# AutomatedBlindOpener.net
KiCad netlist of a schematic drawn in EAGLE
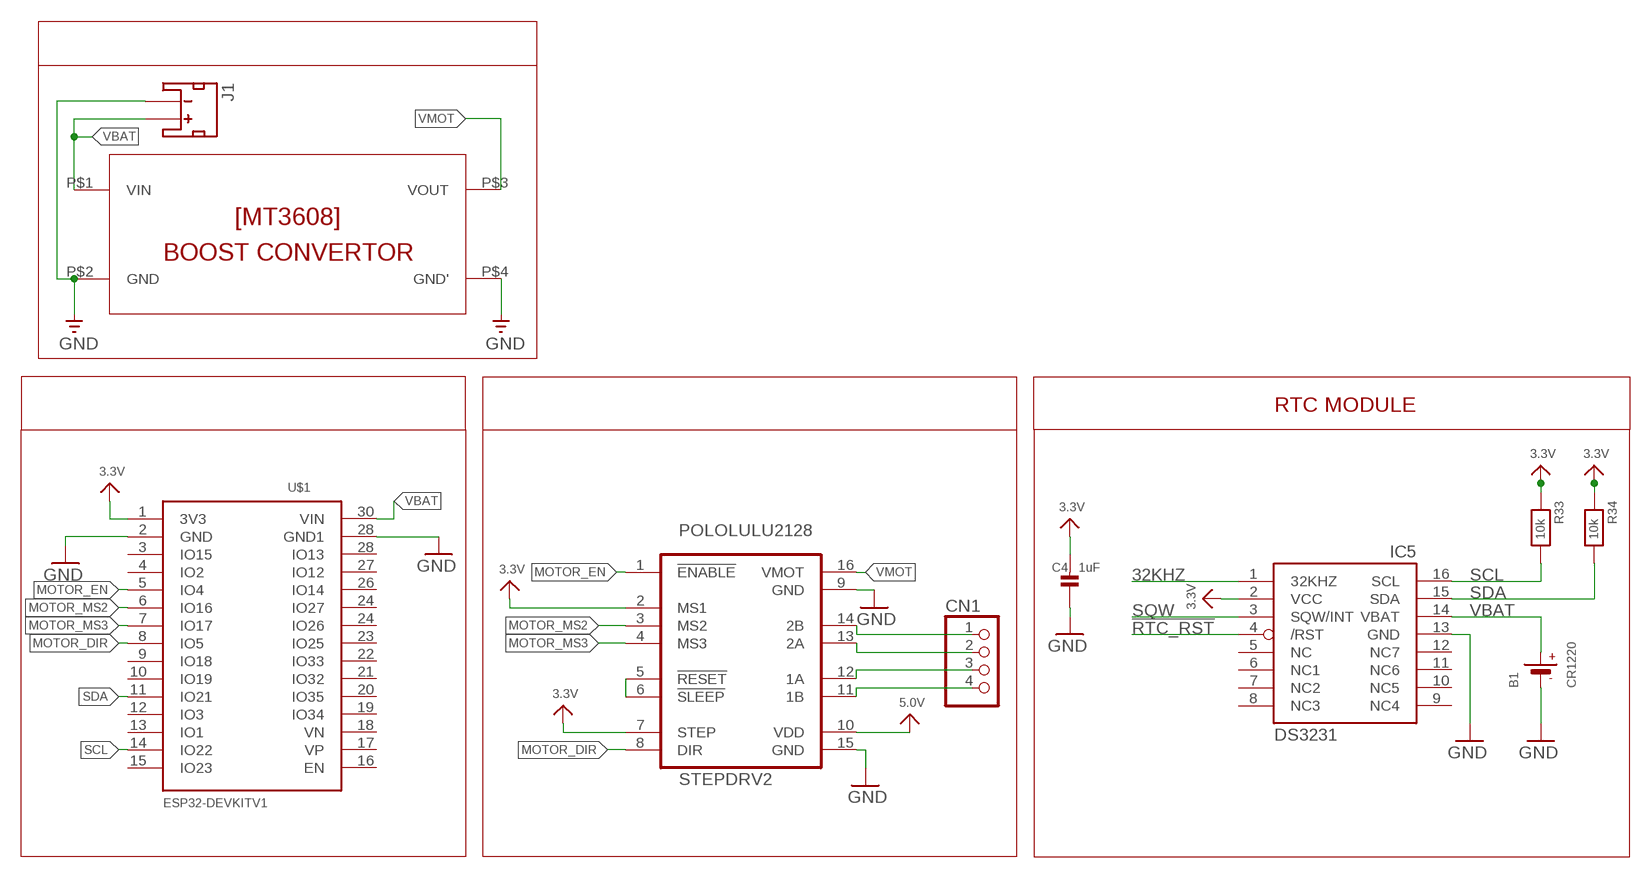
[diagram p0: schematic, sheet 1]

(export (version "E")
  (design (tool "Eeschema 10.0.6"))
  (components
    (comp (ref "B1")
      (value "CR1220")
      (footprint "eagle-import:CR1220")
      (libsource (lib "eagle-import") (part "BATTERYCR1220_SMT"))
    )
    (comp (ref "C4")
      (value "1uF")
      (footprint "eagle-import:0805")
      (libsource (lib "eagle-import") (part "CAP_CERAMIC0805"))
    )
    (comp (ref "CN1")
      (value "JST_4PIN")
      (footprint "eagle-import:JSTPH4")
      (libsource (lib "eagle-import") (part "JST_4PIN"))
    )
    (comp (ref "IC5")
      (value "DS3231/SO")
      (footprint "eagle-import:SO16W")
      (libsource (lib "eagle-import") (part "DS3231/SO"))
    )
    (comp (ref "J1")
      (value "JST_2MM_MALE")
      (footprint "eagle-import:JST-2-SMD")
      (libsource (lib "eagle-import") (part "JST_2MM_MALE"))
    )
    (comp (ref "R33")
      (value "10k")
      (footprint "eagle-import:0805")
      (libsource (lib "eagle-import") (part "RESISTOR0805"))
    )
    (comp (ref "R34")
      (value "10k")
      (footprint "eagle-import:0805")
      (libsource (lib "eagle-import") (part "RESISTOR0805"))
    )
    (comp (ref "STEPDRV2")
      (value "POLOLULU2128")
      (footprint "eagle-import:POLOLULU2128")
      (libsource (lib "eagle-import") (part "POLOLULU2128"))
    )
    (comp (ref "U$1")
      (value "ESP32DEVKITV1")
      (footprint "eagle-import:ESP32-DEVKITV1")
      (libsource (lib "eagle-import") (part "ESP32DEVKITV1"))
    )
    (comp (ref "U$3")
      (value "MT3608")
      (footprint "eagle-import:MT3608")
      (libsource (lib "eagle-import") (part "MT3608"))
    )
  )
  (nets
    (net (code "1") (name "/32KHZ") (class "Default")
      (node (ref "IC5") (pin "1") (pinfunction "32KHZ_1") (pintype "output"))
    )
    (net (code "2") (name "/SQW") (class "Default")
      (node (ref "IC5") (pin "3") (pinfunction "SQW/INT_3") (pintype "output"))
    )
    (net (code "3") (name "/~{RTC_RST}") (class "Default")
      (node (ref "IC5") (pin "4") (pinfunction "/RST_4") (pintype "passive"))
    )
    (net (code "4") (name "3.3V") (class "Default")
      (node (ref "C4") (pin "2") (pinfunction "P$2_2") (pintype "passive"))
      (node (ref "IC5") (pin "2") (pinfunction "VCC_2") (pintype "power_in"))
      (node (ref "R33") (pin "1") (pinfunction "1_1") (pintype "passive"))
      (node (ref "R34") (pin "1") (pinfunction "1_1") (pintype "passive"))
      (node (ref "STEPDRV2") (pin "2") (pinfunction "MS1_2") (pintype "input"))
      (node (ref "STEPDRV2") (pin "7") (pinfunction "STEP_7") (pintype "input"))
      (node (ref "U$1") (pin "1") (pinfunction "3V3_1") (pintype "bidirectional"))
    )
    (net (code "5") (name "5.0V") (class "Default")
      (node (ref "STEPDRV2") (pin "10") (pinfunction "VDD_10") (pintype "power_in"))
    )
    (net (code "6") (name "GND") (class "Default")
      (node (ref "B1") (pin "-") (pinfunction "-_-") (pintype "passive"))
      (node (ref "C4") (pin "1") (pinfunction "P$1_1") (pintype "passive"))
      (node (ref "IC5") (pin "13") (pinfunction "GND_13") (pintype "power_in"))
      (node (ref "J1") (pin "1") (pinfunction "-_1") (pintype "bidirectional"))
      (node (ref "STEPDRV2") (pin "15") (pinfunction "GND_15") (pintype "power_in"))
      (node (ref "STEPDRV2") (pin "9") (pinfunction "GND_9") (pintype "power_in"))
      (node (ref "U$1") (pin "2") (pinfunction "GND_2") (pintype "bidirectional"))
      (node (ref "U$1") (pin "28") (pinfunction "GND1_28") (pintype "bidirectional"))
      (node (ref "U$3") (pin "P$2") (pinfunction "GND_P$2") (pintype "bidirectional"))
      (node (ref "U$3") (pin "P$4") (pinfunction "GND'_P$4") (pintype "bidirectional"))
    )
    (net (code "7") (name "MOTOR_DIR") (class "Default")
      (node (ref "STEPDRV2") (pin "8") (pinfunction "DIR_8") (pintype "input"))
      (node (ref "U$1") (pin "8") (pinfunction "IO5_8") (pintype "bidirectional"))
    )
    (net (code "8") (name "MOTOR_EN") (class "Default")
      (node (ref "STEPDRV2") (pin "1") (pinfunction "~{ENABLE}_1") (pintype "input"))
      (node (ref "U$1") (pin "5") (pinfunction "IO4_5") (pintype "bidirectional"))
    )
    (net (code "9") (name "MOTOR_MS2") (class "Default")
      (node (ref "STEPDRV2") (pin "3") (pinfunction "MS2_3") (pintype "input"))
      (node (ref "U$1") (pin "6") (pinfunction "IO16_6") (pintype "bidirectional"))
    )
    (net (code "10") (name "MOTOR_MS3") (class "Default")
      (node (ref "STEPDRV2") (pin "4") (pinfunction "MS3_4") (pintype "input"))
      (node (ref "U$1") (pin "7") (pinfunction "IO17_7") (pintype "bidirectional"))
    )
    (net (code "11") (name "Net-(STEPDRV2-1A)") (class "Default")
      (node (ref "CN1") (pin "3") (pinfunction "3_3") (pintype "passive"))
      (node (ref "STEPDRV2") (pin "12") (pinfunction "1A_12") (pintype "output"))
    )
    (net (code "12") (name "Net-(STEPDRV2-1B)") (class "Default")
      (node (ref "CN1") (pin "4") (pinfunction "4_4") (pintype "passive"))
      (node (ref "STEPDRV2") (pin "11") (pinfunction "1B_11") (pintype "output"))
    )
    (net (code "13") (name "Net-(STEPDRV2-2A)") (class "Default")
      (node (ref "CN1") (pin "2") (pinfunction "2_2") (pintype "passive"))
      (node (ref "STEPDRV2") (pin "13") (pinfunction "2A_13") (pintype "output"))
    )
    (net (code "14") (name "Net-(STEPDRV2-2B)") (class "Default")
      (node (ref "CN1") (pin "1") (pinfunction "1_1") (pintype "passive"))
      (node (ref "STEPDRV2") (pin "14") (pinfunction "2B_14") (pintype "output"))
    )
    (net (code "15") (name "Net-(STEPDRV2-~{RESET})") (class "Default")
      (node (ref "STEPDRV2") (pin "5") (pinfunction "~{RESET}_5") (pintype "input"))
      (node (ref "STEPDRV2") (pin "6") (pinfunction "~{SLEEP}_6") (pintype "input"))
    )
    (net (code "16") (name "SCL") (class "Default")
      (node (ref "IC5") (pin "16") (pinfunction "SCL_16") (pintype "bidirectional"))
      (node (ref "R33") (pin "2") (pinfunction "2_2") (pintype "passive"))
      (node (ref "U$1") (pin "14") (pinfunction "IO22_14") (pintype "bidirectional"))
    )
    (net (code "17") (name "SDA") (class "Default")
      (node (ref "IC5") (pin "15") (pinfunction "SDA_15") (pintype "bidirectional"))
      (node (ref "R34") (pin "2") (pinfunction "2_2") (pintype "passive"))
      (node (ref "U$1") (pin "11") (pinfunction "IO21_11") (pintype "bidirectional"))
    )
    (net (code "18") (name "VBAT") (class "Default")
      (node (ref "B1") (pin "+$1") (pinfunction "+_+$1") (pintype "passive"))
      (node (ref "IC5") (pin "14") (pinfunction "VBAT_14") (pintype "power_in"))
      (node (ref "J1") (pin "2") (pinfunction "+_2") (pintype "bidirectional"))
      (node (ref "U$1") (pin "30") (pinfunction "VIN_30") (pintype "bidirectional"))
      (node (ref "U$3") (pin "P$1") (pinfunction "VIN_P$1") (pintype "bidirectional"))
    )
    (net (code "19") (name "VMOT") (class "Default")
      (node (ref "STEPDRV2") (pin "16") (pinfunction "VMOT_16") (pintype "power_in"))
      (node (ref "U$3") (pin "P$3") (pinfunction "VOUT_P$3") (pintype "bidirectional"))
    )
    (net (code "20") (name "unconnected-(IC5-NC-Pad5)") (class "Default")
      (node (ref "IC5") (pin "5") (pinfunction "NC_5") (pintype "no_connect"))
    )
    (net (code "21") (name "unconnected-(IC5-NC1-Pad6)") (class "Default")
      (node (ref "IC5") (pin "6") (pinfunction "NC1_6") (pintype "no_connect"))
    )
    (net (code "22") (name "unconnected-(IC5-NC2-Pad7)") (class "Default")
      (node (ref "IC5") (pin "7") (pinfunction "NC2_7") (pintype "no_connect"))
    )
    (net (code "23") (name "unconnected-(IC5-NC3-Pad8)") (class "Default")
      (node (ref "IC5") (pin "8") (pinfunction "NC3_8") (pintype "no_connect"))
    )
    (net (code "24") (name "unconnected-(IC5-NC4-Pad9)") (class "Default")
      (node (ref "IC5") (pin "9") (pinfunction "NC4_9") (pintype "no_connect"))
    )
    (net (code "25") (name "unconnected-(IC5-NC5-Pad10)") (class "Default")
      (node (ref "IC5") (pin "10") (pinfunction "NC5_10") (pintype "no_connect"))
    )
    (net (code "26") (name "unconnected-(IC5-NC6-Pad11)") (class "Default")
      (node (ref "IC5") (pin "11") (pinfunction "NC6_11") (pintype "no_connect"))
    )
    (net (code "27") (name "unconnected-(IC5-NC7-Pad12)") (class "Default")
      (node (ref "IC5") (pin "12") (pinfunction "NC7_12") (pintype "no_connect"))
    )
    (net (code "28") (name "unconnected-(J1-PAD1-PadNC1)") (class "Default")
      (node (ref "J1") (pin "NC1") (pinfunction "PAD1_NC1") (pintype "bidirectional"))
    )
    (net (code "29") (name "unconnected-(J1-PAD2-PadNC2)") (class "Default")
      (node (ref "J1") (pin "NC2") (pinfunction "PAD2_NC2") (pintype "bidirectional"))
    )
    (net (code "30") (name "unconnected-(U$1-EN-Pad16)") (class "Default")
      (node (ref "U$1") (pin "16") (pinfunction "EN_16") (pintype "bidirectional"))
    )
    (net (code "31") (name "unconnected-(U$1-IO1-Pad13)") (class "Default")
      (node (ref "U$1") (pin "13") (pinfunction "IO1_13") (pintype "bidirectional"))
    )
    (net (code "32") (name "unconnected-(U$1-IO2-Pad4)") (class "Default")
      (node (ref "U$1") (pin "4") (pinfunction "IO2_4") (pintype "bidirectional"))
    )
    (net (code "33") (name "unconnected-(U$1-IO3-Pad12)") (class "Default")
      (node (ref "U$1") (pin "12") (pinfunction "IO3_12") (pintype "bidirectional"))
    )
    (net (code "34") (name "unconnected-(U$1-IO12-Pad27)") (class "Default")
      (node (ref "U$1") (pin "27") (pinfunction "IO12_27") (pintype "bidirectional"))
    )
    (net (code "35") (name "unconnected-(U$1-IO13-Pad28)") (class "Default")
      (node (ref "U$1") (pin "28") (pinfunction "IO13_28") (pintype "bidirectional"))
    )
    (net (code "36") (name "unconnected-(U$1-IO14-Pad26)") (class "Default")
      (node (ref "U$1") (pin "26") (pinfunction "IO14_26") (pintype "bidirectional"))
    )
    (net (code "37") (name "unconnected-(U$1-IO15-Pad3)") (class "Default")
      (node (ref "U$1") (pin "3") (pinfunction "IO15_3") (pintype "bidirectional"))
    )
    (net (code "38") (name "unconnected-(U$1-IO18-Pad9)") (class "Default")
      (node (ref "U$1") (pin "9") (pinfunction "IO18_9") (pintype "bidirectional"))
    )
    (net (code "39") (name "unconnected-(U$1-IO19-Pad10)") (class "Default")
      (node (ref "U$1") (pin "10") (pinfunction "IO19_10") (pintype "bidirectional"))
    )
    (net (code "40") (name "unconnected-(U$1-IO23-Pad15)") (class "Default")
      (node (ref "U$1") (pin "15") (pinfunction "IO23_15") (pintype "bidirectional"))
    )
    (net (code "41") (name "unconnected-(U$1-IO25-Pad23)") (class "Default")
      (node (ref "U$1") (pin "23") (pinfunction "IO25_23") (pintype "bidirectional"))
    )
    (net (code "42") (name "unconnected-(U$1-IO26-Pad24)") (class "Default")
      (node (ref "U$1") (pin "24") (pinfunction "IO26_24") (pintype "bidirectional"))
    )
    (net (code "43") (name "unconnected-(U$1-IO27-Pad24)") (class "Default")
      (node (ref "U$1") (pin "24") (pinfunction "IO27_24") (pintype "bidirectional"))
    )
    (net (code "44") (name "unconnected-(U$1-IO32-Pad21)") (class "Default")
      (node (ref "U$1") (pin "21") (pinfunction "IO32_21") (pintype "bidirectional"))
    )
    (net (code "45") (name "unconnected-(U$1-IO33-Pad22)") (class "Default")
      (node (ref "U$1") (pin "22") (pinfunction "IO33_22") (pintype "bidirectional"))
    )
    (net (code "46") (name "unconnected-(U$1-IO34-Pad19)") (class "Default")
      (node (ref "U$1") (pin "19") (pinfunction "IO34_19") (pintype "bidirectional"))
    )
    (net (code "47") (name "unconnected-(U$1-IO35-Pad20)") (class "Default")
      (node (ref "U$1") (pin "20") (pinfunction "IO35_20") (pintype "bidirectional"))
    )
    (net (code "48") (name "unconnected-(U$1-VN-Pad18)") (class "Default")
      (node (ref "U$1") (pin "18") (pinfunction "VN_18") (pintype "bidirectional"))
    )
    (net (code "49") (name "unconnected-(U$1-VP-Pad17)") (class "Default")
      (node (ref "U$1") (pin "17") (pinfunction "VP_17") (pintype "bidirectional"))
    )
  )
)
